# GPRS.net
KiCad netlist of a schematic drawn in Altium Designer
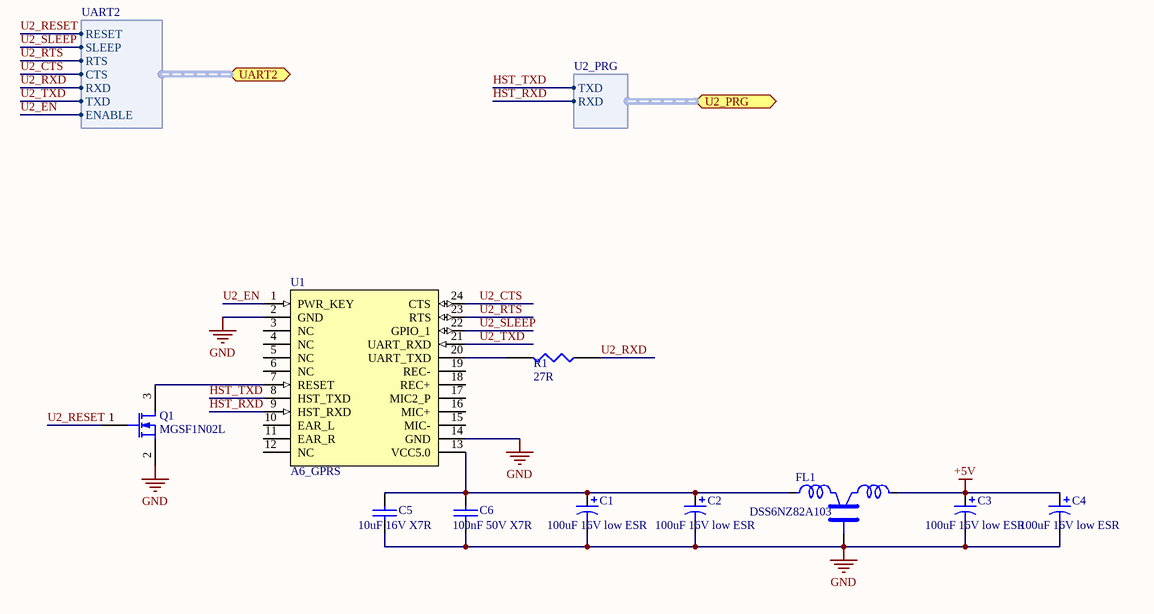
[diagram p0: GPRS.SchDoc]

(export (version "E")
  (design (tool "Eeschema 10.0.6"))
  (components
    (comp (ref "C1")
      (value "100uF 16V low ESR")
      (footprint "Capacitor Polar Radial Cylinder:CAPPR2-5x11")
      (description "Polarized Capacitor (Radial)")
      (libsource (lib "Miscellaneous Devices") (part "Cap Pol1"))
    )
    (comp (ref "C2")
      (value "100uF 16V low ESR")
      (footprint "Capacitor Polar Radial Cylinder:CAPPR2-5x11")
      (description "Polarized Capacitor (Radial)")
      (libsource (lib "Miscellaneous Devices") (part "Cap Pol1"))
    )
    (comp (ref "C3")
      (value "100uF 16V low ESR")
      (footprint "Capacitor Polar Radial Cylinder:CAPPR2-5x11")
      (description "Polarized Capacitor (Radial)")
      (libsource (lib "Miscellaneous Devices") (part "Cap Pol1"))
    )
    (comp (ref "C4")
      (value "100uF 16V low ESR")
      (footprint "Capacitor Polar Radial Cylinder:CAPPR2-5x11")
      (description "Polarized Capacitor (Radial)")
      (libsource (lib "Miscellaneous Devices") (part "Cap Pol1"))
    )
    (comp (ref "C5")
      (value "10uF 16V X7R")
      (footprint "IPC-7352 Chip_Capacitor_N:CAPC3216N")
      (libsource (lib "*") (part "CAP"))
    )
    (comp (ref "C6")
      (value "100nF 50V X7R")
      (footprint "IPC-7352 Chip_Capacitor_N:CAPC2012N")
      (libsource (lib "*") (part "CAP"))
    )
    (comp (ref "FL1")
      (value "DSS6NZ82A103")
      (footprint "UserPcbLib:DSS6")
      (description "Murata EMI suppression filter")
      (fields (field (name "MANUFACTURER") "Murata"))
      (libsource (lib "UserSchlib") (part "DSS6"))
    )
    (comp (ref "Q1")
      (value "MGSF1N02L")
      (footprint "SOT23_N:SOT23-3N")
      (description "N-Channel MOSFET")
      (fields (field (name "PUBLISHER") "Altium Limited"))
      (libsource (lib "Miscellaneous Devices") (part "MOSFET-N"))
    )
    (comp (ref "R1")
      (value "27R")
      (footprint "IPC-7352 Chip_Resistor_N:RESC2012N")
      (libsource (lib "*") (part "RES1"))
    )
    (comp (ref "U1")
      (value "A6_GPRS")
      (footprint "UserPcbLib:A6_GPRS_MOD")
      (description "GPRS module")
      (fields (field (name "MANUFACTURER") "Ai ThinkerTecnology"))
      (libsource (lib "UserSchlib") (part "A6_GPRS_Module"))
    )
  )
  (nets
    (net (code "3") (name "+5V") (class "Default")
      (node (ref "C3") (pin "1") (pinfunction "1_1") (pintype "passive"))
      (node (ref "C4") (pin "1") (pinfunction "1_1") (pintype "passive"))
      (node (ref "FL1") (pin "3") (pinfunction "3_3") (pintype "power_in"))
    )
    (net (code "4") (name "/HST_RXD") (class "Default")
      (node (ref "U1") (pin "9") (pinfunction "HST_RXD_9") (pintype "input"))
    )
    (net (code "5") (name "/HST_TXD") (class "Default")
      (node (ref "U1") (pin "8") (pinfunction "HST_TXD_8") (pintype "tri_state"))
    )
    (net (code "6") (name "/U2_CTS") (class "Default")
      (node (ref "U1") (pin "24") (pinfunction "CTS_24") (pintype "bidirectional"))
    )
    (net (code "7") (name "/U2_EN") (class "Default")
      (node (ref "U1") (pin "1") (pinfunction "PWR_KEY_1") (pintype "input"))
    )
    (net (code "8") (name "/U2_RESET") (class "Default")
      (node (ref "Q1") (pin "1") (pinfunction "G_1") (pintype "passive"))
    )
    (net (code "9") (name "/U2_RTS") (class "Default")
      (node (ref "U1") (pin "23") (pinfunction "RTS_23") (pintype "bidirectional"))
    )
    (net (code "10") (name "/U2_RXD") (class "Default")
      (node (ref "R1") (pin "1") (pinfunction "1_1") (pintype "passive"))
    )
    (net (code "11") (name "/U2_SLEEP") (class "Default")
      (node (ref "U1") (pin "22") (pinfunction "GPIO_1_22") (pintype "bidirectional"))
    )
    (net (code "12") (name "/U2_TXD") (class "Default")
      (node (ref "U1") (pin "21") (pinfunction "UART_RXD_21") (pintype "input"))
    )
    (net (code "15") (name "GND") (class "Default")
      (node (ref "C1") (pin "2") (pinfunction "2_2") (pintype "passive"))
      (node (ref "C2") (pin "2") (pinfunction "2_2") (pintype "passive"))
      (node (ref "C3") (pin "2") (pinfunction "2_2") (pintype "passive"))
      (node (ref "C4") (pin "2") (pinfunction "2_2") (pintype "passive"))
      (node (ref "C5") (pin "2") (pintype "passive"))
      (node (ref "C6") (pin "2") (pintype "passive"))
      (node (ref "FL1") (pin "2") (pinfunction "2_2") (pintype "power_in"))
      (node (ref "Q1") (pin "2") (pinfunction "S_2") (pintype "passive"))
      (node (ref "U1") (pin "14") (pinfunction "GND_14") (pintype "power_in"))
      (node (ref "U1") (pin "2") (pinfunction "GND_2") (pintype "power_in"))
    )
    (net (code "16") (name "Net-(Q1-D)") (class "Default")
      (node (ref "Q1") (pin "3") (pinfunction "D_3") (pintype "passive"))
      (node (ref "U1") (pin "7") (pinfunction "RESET_7") (pintype "input"))
    )
    (net (code "17") (name "Net-(U1-UART_TXD)") (class "Default")
      (node (ref "R1") (pin "2") (pinfunction "2_2") (pintype "passive"))
      (node (ref "U1") (pin "20") (pinfunction "UART_TXD_20") (pintype "tri_state"))
    )
    (net (code "18") (name "Net-(U1-VCC5.0)") (class "Default")
      (node (ref "C1") (pin "1") (pinfunction "1_1") (pintype "passive"))
      (node (ref "C2") (pin "1") (pinfunction "1_1") (pintype "passive"))
      (node (ref "C5") (pin "1") (pintype "passive"))
      (node (ref "C6") (pin "1") (pintype "passive"))
      (node (ref "FL1") (pin "1") (pinfunction "1_1") (pintype "power_in"))
      (node (ref "U1") (pin "13") (pinfunction "VCC5.0_13") (pintype "power_in"))
    )
    (net (code "19") (name "unconnected-(U1-EAR_L-Pad10)") (class "Default")
      (node (ref "U1") (pin "10") (pinfunction "EAR_L_10") (pintype "passive"))
    )
    (net (code "20") (name "unconnected-(U1-EAR_R-Pad11)") (class "Default")
      (node (ref "U1") (pin "11") (pinfunction "EAR_R_11") (pintype "passive"))
    )
    (net (code "21") (name "unconnected-(U1-MIC+-Pad16)") (class "Default")
      (node (ref "U1") (pin "16") (pinfunction "MIC+_16") (pintype "passive"))
    )
    (net (code "22") (name "unconnected-(U1-MIC--Pad15)") (class "Default")
      (node (ref "U1") (pin "15") (pinfunction "MIC-_15") (pintype "passive"))
    )
    (net (code "23") (name "unconnected-(U1-MIC2_P-Pad17)") (class "Default")
      (node (ref "U1") (pin "17") (pinfunction "MIC2_P_17") (pintype "passive"))
    )
    (net (code "24") (name "unconnected-(U1-NC-Pad3)") (class "Default")
      (node (ref "U1") (pin "3") (pinfunction "NC_3") (pintype "power_in"))
    )
    (net (code "25") (name "unconnected-(U1-NC-Pad4)") (class "Default")
      (node (ref "U1") (pin "4") (pinfunction "NC_4") (pintype "power_in"))
    )
    (net (code "26") (name "unconnected-(U1-NC-Pad5)") (class "Default")
      (node (ref "U1") (pin "5") (pinfunction "NC_5") (pintype "power_in"))
    )
    (net (code "27") (name "unconnected-(U1-NC-Pad6)") (class "Default")
      (node (ref "U1") (pin "6") (pinfunction "NC_6") (pintype "power_in"))
    )
    (net (code "28") (name "unconnected-(U1-NC-Pad12)") (class "Default")
      (node (ref "U1") (pin "12") (pinfunction "NC_12") (pintype "power_in"))
    )
    (net (code "29") (name "unconnected-(U1-REC+-Pad18)") (class "Default")
      (node (ref "U1") (pin "18") (pinfunction "REC+_18") (pintype "passive"))
    )
    (net (code "30") (name "unconnected-(U1-REC--Pad19)") (class "Default")
      (node (ref "U1") (pin "19") (pinfunction "REC-_19") (pintype "passive"))
    )
  )
)
